# DressCode.net
KiCad netlist of a schematic drawn in EAGLE
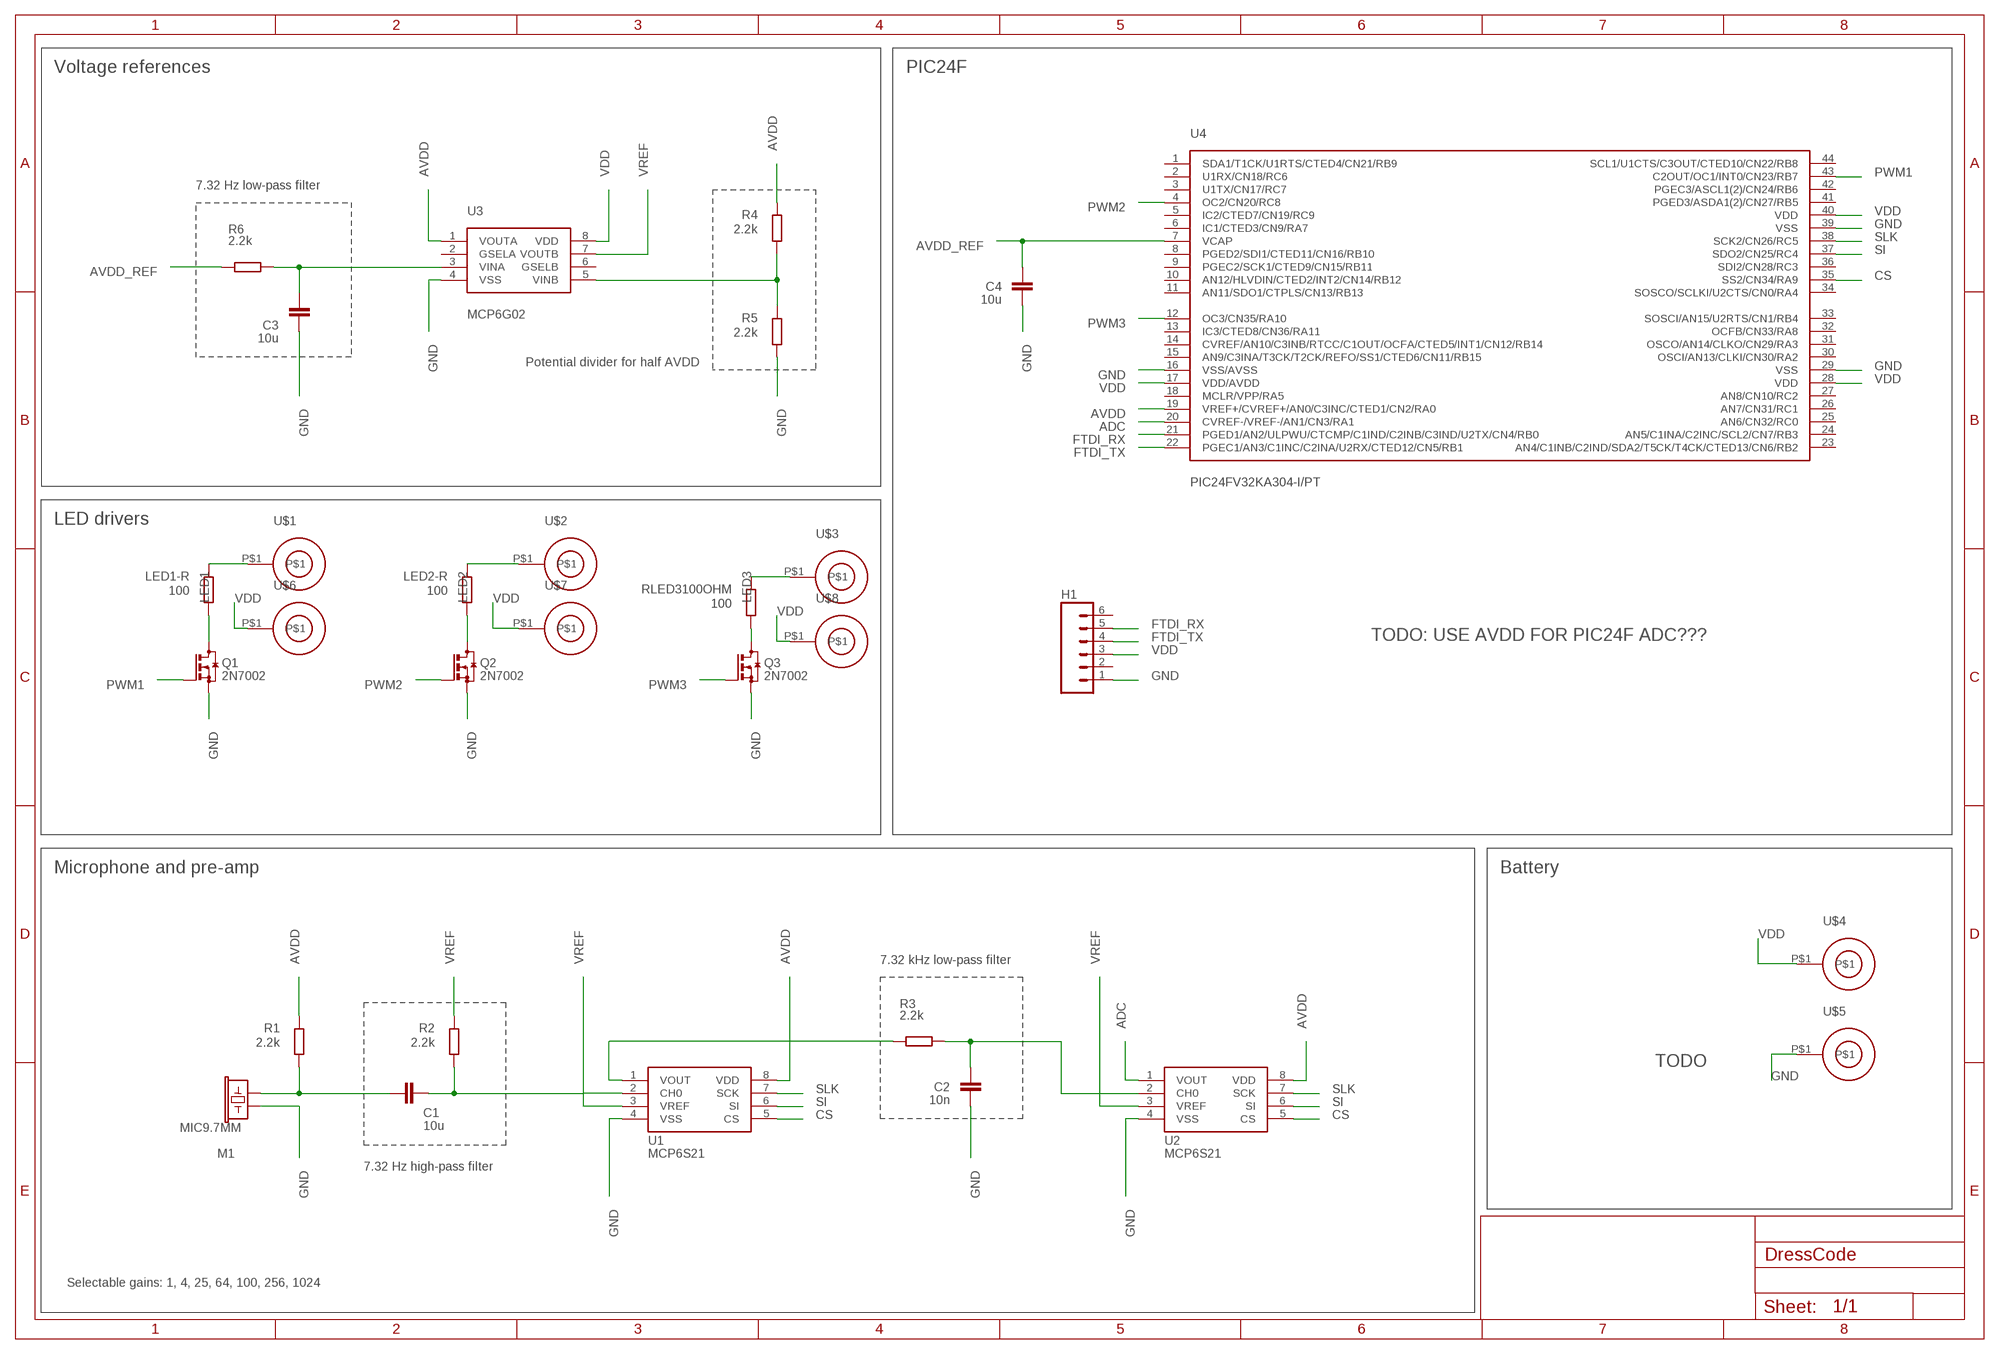
[diagram p0: schematic, sheet 1]

(export (version "E")
  (design (tool "Eeschema 10.0.6"))
  (components
    (comp (ref "C1")
      (value "10u")
      (footprint "eagle-import:C0805")
      (libsource (lib "eagle-import") (part "C-EUC0805"))
    )
    (comp (ref "C2")
      (value "10n")
      (footprint "eagle-import:C0805")
      (libsource (lib "eagle-import") (part "C-EUC0805"))
    )
    (comp (ref "C3")
      (value "10u")
      (footprint "eagle-import:C0805")
      (libsource (lib "eagle-import") (part "C-EUC0805"))
    )
    (comp (ref "C4")
      (value "10u")
      (footprint "eagle-import:C0805")
      (libsource (lib "eagle-import") (part "C-EUC0805"))
    )
    (comp (ref "H1")
      (value "M06LOCK")
      (footprint "eagle-import:1X06_LOCK")
      (libsource (lib "eagle-import") (part "M06LOCK"))
    )
    (comp (ref "LED1-R")
      (value "100")
      (footprint "eagle-import:R0805")
      (libsource (lib "eagle-import") (part "R-EU_R0805"))
    )
    (comp (ref "LED2-R")
      (value "100")
      (footprint "eagle-import:R0805")
      (libsource (lib "eagle-import") (part "R-EU_R0805"))
    )
    (comp (ref "M1")
      (value "MIC9.7MM")
      (footprint "eagle-import:MIC-9.7MM")
      (libsource (lib "eagle-import") (part "MIC9.7MM"))
    )
    (comp (ref "Q1")
      (value "2N7002")
      (footprint "eagle-import:SOT23")
      (libsource (lib "eagle-import") (part "BSS123"))
    )
    (comp (ref "Q2")
      (value "2N7002")
      (footprint "eagle-import:SOT23")
      (libsource (lib "eagle-import") (part "BSS123"))
    )
    (comp (ref "Q3")
      (value "2N7002")
      (footprint "eagle-import:SOT23")
      (libsource (lib "eagle-import") (part "BSS123"))
    )
    (comp (ref "R1")
      (value "2.2k")
      (footprint "eagle-import:R0805")
      (libsource (lib "eagle-import") (part "R-EU_R0805"))
    )
    (comp (ref "R2")
      (value "2.2k")
      (footprint "eagle-import:R0805")
      (libsource (lib "eagle-import") (part "R-EU_R0805"))
    )
    (comp (ref "R3")
      (value "2.2k")
      (footprint "eagle-import:R0805")
      (libsource (lib "eagle-import") (part "R-EU_R0805"))
    )
    (comp (ref "R4")
      (value "2.2k")
      (footprint "eagle-import:R0805")
      (libsource (lib "eagle-import") (part "R-EU_R0805"))
    )
    (comp (ref "R5")
      (value "2.2k")
      (footprint "eagle-import:R0805")
      (libsource (lib "eagle-import") (part "R-EU_R0805"))
    )
    (comp (ref "R6")
      (value "2.2k")
      (footprint "eagle-import:R0805")
      (libsource (lib "eagle-import") (part "R-EU_R0805"))
    )
    (comp (ref "RLED3100OHM")
      (value "100")
      (footprint "eagle-import:R0805")
      (libsource (lib "eagle-import") (part "R-EU_R0805"))
    )
    (comp (ref "U$1")
      (value "SEWING-VIA")
      (footprint "eagle-import:SEWING-VIA2MM")
      (libsource (lib "eagle-import") (part "SEWING-VIA"))
    )
    (comp (ref "U$2")
      (value "SEWING-VIA")
      (footprint "eagle-import:SEWING-VIA2MM")
      (libsource (lib "eagle-import") (part "SEWING-VIA"))
    )
    (comp (ref "U$3")
      (value "SEWING-VIA")
      (footprint "eagle-import:SEWING-VIA2MM")
      (libsource (lib "eagle-import") (part "SEWING-VIA"))
    )
    (comp (ref "U$4")
      (value "SEWING-VIA")
      (footprint "eagle-import:SEWING-VIA2MM")
      (libsource (lib "eagle-import") (part "SEWING-VIA"))
    )
    (comp (ref "U$5")
      (value "SEWING-VIA")
      (footprint "eagle-import:SEWING-VIA2MM")
      (libsource (lib "eagle-import") (part "SEWING-VIA"))
    )
    (comp (ref "U$6")
      (value "SEWING-VIA")
      (footprint "eagle-import:SEWING-VIA2MM")
      (libsource (lib "eagle-import") (part "SEWING-VIA"))
    )
    (comp (ref "U$7")
      (value "SEWING-VIA")
      (footprint "eagle-import:SEWING-VIA2MM")
      (libsource (lib "eagle-import") (part "SEWING-VIA"))
    )
    (comp (ref "U$8")
      (value "SEWING-VIA")
      (footprint "eagle-import:SEWING-VIA2MM")
      (libsource (lib "eagle-import") (part "SEWING-VIA"))
    )
    (comp (ref "U1")
      (value "MCP6S21")
      (footprint "eagle-import:SOIC-8")
      (libsource (lib "eagle-import") (part "MCP6S21"))
    )
    (comp (ref "U2")
      (value "MCP6S21")
      (footprint "eagle-import:SOIC-8")
      (libsource (lib "eagle-import") (part "MCP6S21"))
    )
    (comp (ref "U3")
      (value "MCP6G02")
      (footprint "eagle-import:SOIC-8")
      (libsource (lib "eagle-import") (part "MCP6G02"))
    )
    (comp (ref "U4")
      (value "PIC24FV32KA304-I/PT")
      (footprint "eagle-import:TQFP44")
      (libsource (lib "eagle-import") (part "PIC24FV32KA304-I/PT"))
    )
  )
  (nets
    (net (code "1") (name "/ADC") (class "Default")
      (node (ref "U2") (pin "1") (pinfunction "VOUT_1") (pintype "bidirectional"))
      (node (ref "U4") (pin "20") (pinfunction "CVREF-/VREF-/AN1/CN3/RA1_20") (pintype "bidirectional"))
    )
    (net (code "2") (name "/AVDD") (class "Default")
      (node (ref "R1") (pin "2") (pinfunction "2_2") (pintype "passive"))
      (node (ref "R4") (pin "2") (pinfunction "2_2") (pintype "passive"))
      (node (ref "U1") (pin "8") (pinfunction "VDD_8") (pintype "bidirectional"))
      (node (ref "U2") (pin "8") (pinfunction "VDD_8") (pintype "bidirectional"))
      (node (ref "U3") (pin "1") (pinfunction "VOUTA_1") (pintype "bidirectional"))
      (node (ref "U4") (pin "19") (pinfunction "VREF+/CVREF+/AN0/C3INC/CTED1/CN2/RA0_19") (pintype "bidirectional"))
    )
    (net (code "3") (name "/AVDD_REF") (class "Default")
      (node (ref "C4") (pin "2") (pinfunction "2_2") (pintype "passive"))
      (node (ref "R6") (pin "1") (pinfunction "1_1") (pintype "passive"))
      (node (ref "U4") (pin "7") (pinfunction "VCAP_7") (pintype "bidirectional"))
    )
    (net (code "4") (name "/CS") (class "Default")
      (node (ref "U1") (pin "5") (pinfunction "CS_5") (pintype "bidirectional"))
      (node (ref "U2") (pin "5") (pinfunction "CS_5") (pintype "bidirectional"))
      (node (ref "U4") (pin "35") (pinfunction "SS2/CN34/RA9_35") (pintype "bidirectional"))
    )
    (net (code "5") (name "/FTDI_RX") (class "Default")
      (node (ref "H1") (pin "5") (pinfunction "5_5") (pintype "passive"))
      (node (ref "U4") (pin "21") (pinfunction "PGED1/AN2/ULPWU/CTCMP/C1IND/C2INB/C3IND/U2TX/CN4/RB0_21") (pintype "bidirectional"))
    )
    (net (code "6") (name "/FTDI_TX") (class "Default")
      (node (ref "H1") (pin "4") (pinfunction "4_4") (pintype "passive"))
      (node (ref "U4") (pin "22") (pinfunction "PGEC1/AN3/C1INC/C2INA/U2RX/CTED12/CN5/RB1_22") (pintype "bidirectional"))
    )
    (net (code "7") (name "/GND") (class "Default")
      (node (ref "C2") (pin "2") (pinfunction "2_2") (pintype "passive"))
      (node (ref "C3") (pin "1") (pinfunction "1_1") (pintype "passive"))
      (node (ref "C4") (pin "1") (pinfunction "1_1") (pintype "passive"))
      (node (ref "H1") (pin "1") (pinfunction "1_1") (pintype "passive"))
      (node (ref "M1") (pin "2") (pinfunction "2_2") (pintype "passive"))
      (node (ref "Q1") (pin "2") (pinfunction "S_2") (pintype "passive"))
      (node (ref "Q2") (pin "2") (pinfunction "S_2") (pintype "passive"))
      (node (ref "Q3") (pin "2") (pinfunction "S_2") (pintype "passive"))
      (node (ref "R5") (pin "1") (pinfunction "1_1") (pintype "passive"))
      (node (ref "U$5") (pin "P$1") (pinfunction "P$1_P$1") (pintype "bidirectional"))
      (node (ref "U1") (pin "4") (pinfunction "VSS_4") (pintype "bidirectional"))
      (node (ref "U2") (pin "4") (pinfunction "VSS_4") (pintype "bidirectional"))
      (node (ref "U3") (pin "4") (pinfunction "VSS_4") (pintype "bidirectional"))
      (node (ref "U4") (pin "16") (pinfunction "VSS/AVSS_16") (pintype "bidirectional"))
      (node (ref "U4") (pin "29") (pinfunction "VSS_29") (pintype "bidirectional"))
      (node (ref "U4") (pin "39") (pinfunction "VSS_39") (pintype "bidirectional"))
    )
    (net (code "8") (name "/LED1") (class "Default")
      (node (ref "LED1-R") (pin "2") (pinfunction "2_2") (pintype "passive"))
      (node (ref "U$1") (pin "P$1") (pinfunction "P$1_P$1") (pintype "bidirectional"))
    )
    (net (code "9") (name "/LED2") (class "Default")
      (node (ref "LED2-R") (pin "2") (pinfunction "2_2") (pintype "passive"))
      (node (ref "U$2") (pin "P$1") (pinfunction "P$1_P$1") (pintype "bidirectional"))
    )
    (net (code "10") (name "/LED3") (class "Default")
      (node (ref "RLED3100OHM") (pin "2") (pinfunction "2_2") (pintype "passive"))
      (node (ref "U$3") (pin "P$1") (pinfunction "P$1_P$1") (pintype "bidirectional"))
    )
    (net (code "11") (name "/PWM1") (class "Default")
      (node (ref "Q1") (pin "1") (pinfunction "G_1") (pintype "passive"))
      (node (ref "U4") (pin "43") (pinfunction "C2OUT/OC1/INT0/CN23/RB7_43") (pintype "bidirectional"))
    )
    (net (code "12") (name "/PWM2") (class "Default")
      (node (ref "Q2") (pin "1") (pinfunction "G_1") (pintype "passive"))
      (node (ref "U4") (pin "4") (pinfunction "OC2/CN20/RC8_4") (pintype "bidirectional"))
    )
    (net (code "13") (name "/PWM3") (class "Default")
      (node (ref "Q3") (pin "1") (pinfunction "G_1") (pintype "passive"))
      (node (ref "U4") (pin "12") (pinfunction "OC3/CN35/RA10_12") (pintype "bidirectional"))
    )
    (net (code "14") (name "/SI") (class "Default")
      (node (ref "U1") (pin "6") (pinfunction "SI_6") (pintype "bidirectional"))
      (node (ref "U2") (pin "6") (pinfunction "SI_6") (pintype "bidirectional"))
      (node (ref "U4") (pin "37") (pinfunction "SDO2/CN25/RC4_37") (pintype "bidirectional"))
    )
    (net (code "15") (name "/SLK") (class "Default")
      (node (ref "U1") (pin "7") (pinfunction "SCK_7") (pintype "bidirectional"))
      (node (ref "U2") (pin "7") (pinfunction "SCK_7") (pintype "bidirectional"))
      (node (ref "U4") (pin "38") (pinfunction "SCK2/CN26/RC5_38") (pintype "bidirectional"))
    )
    (net (code "16") (name "/VDD") (class "Default")
      (node (ref "H1") (pin "3") (pinfunction "3_3") (pintype "passive"))
      (node (ref "U$4") (pin "P$1") (pinfunction "P$1_P$1") (pintype "bidirectional"))
      (node (ref "U$6") (pin "P$1") (pinfunction "P$1_P$1") (pintype "bidirectional"))
      (node (ref "U$7") (pin "P$1") (pinfunction "P$1_P$1") (pintype "bidirectional"))
      (node (ref "U$8") (pin "P$1") (pinfunction "P$1_P$1") (pintype "bidirectional"))
      (node (ref "U3") (pin "8") (pinfunction "VDD_8") (pintype "bidirectional"))
      (node (ref "U4") (pin "17") (pinfunction "VDD/AVDD_17") (pintype "bidirectional"))
      (node (ref "U4") (pin "28") (pinfunction "VDD_28") (pintype "bidirectional"))
      (node (ref "U4") (pin "40") (pinfunction "VDD_40") (pintype "bidirectional"))
    )
    (net (code "17") (name "/VREF") (class "Default")
      (node (ref "R2") (pin "2") (pinfunction "2_2") (pintype "passive"))
      (node (ref "U1") (pin "3") (pinfunction "VREF_3") (pintype "bidirectional"))
      (node (ref "U2") (pin "3") (pinfunction "VREF_3") (pintype "bidirectional"))
      (node (ref "U3") (pin "7") (pinfunction "VOUTB_7") (pintype "bidirectional"))
    )
    (net (code "18") (name "Net-(C1-Pad1)") (class "Default")
      (node (ref "C1") (pin "1") (pinfunction "1_1") (pintype "passive"))
      (node (ref "M1") (pin "1") (pinfunction "1_1") (pintype "passive"))
      (node (ref "R1") (pin "1") (pinfunction "1_1") (pintype "passive"))
    )
    (net (code "19") (name "Net-(Q1-D)") (class "Default")
      (node (ref "LED1-R") (pin "1") (pinfunction "1_1") (pintype "passive"))
      (node (ref "Q1") (pin "3") (pinfunction "D_3") (pintype "passive"))
    )
    (net (code "20") (name "Net-(Q2-D)") (class "Default")
      (node (ref "LED2-R") (pin "1") (pinfunction "1_1") (pintype "passive"))
      (node (ref "Q2") (pin "3") (pinfunction "D_3") (pintype "passive"))
    )
    (net (code "21") (name "Net-(Q3-D)") (class "Default")
      (node (ref "Q3") (pin "3") (pinfunction "D_3") (pintype "passive"))
      (node (ref "RLED3100OHM") (pin "1") (pinfunction "1_1") (pintype "passive"))
    )
    (net (code "22") (name "Net-(U1-CH0)") (class "Default")
      (node (ref "C1") (pin "2") (pinfunction "2_2") (pintype "passive"))
      (node (ref "R2") (pin "1") (pinfunction "1_1") (pintype "passive"))
      (node (ref "U1") (pin "2") (pinfunction "CH0_2") (pintype "bidirectional"))
    )
    (net (code "23") (name "Net-(U1-VOUT)") (class "Default")
      (node (ref "R3") (pin "1") (pinfunction "1_1") (pintype "passive"))
      (node (ref "U1") (pin "1") (pinfunction "VOUT_1") (pintype "bidirectional"))
    )
    (net (code "24") (name "Net-(U2-CH0)") (class "Default")
      (node (ref "C2") (pin "1") (pinfunction "1_1") (pintype "passive"))
      (node (ref "R3") (pin "2") (pinfunction "2_2") (pintype "passive"))
      (node (ref "U2") (pin "2") (pinfunction "CH0_2") (pintype "bidirectional"))
    )
    (net (code "25") (name "Net-(U3-VINA)") (class "Default")
      (node (ref "C3") (pin "2") (pinfunction "2_2") (pintype "passive"))
      (node (ref "R6") (pin "2") (pinfunction "2_2") (pintype "passive"))
      (node (ref "U3") (pin "3") (pinfunction "VINA_3") (pintype "bidirectional"))
    )
    (net (code "26") (name "Net-(U3-VINB)") (class "Default")
      (node (ref "R4") (pin "1") (pinfunction "1_1") (pintype "passive"))
      (node (ref "R5") (pin "2") (pinfunction "2_2") (pintype "passive"))
      (node (ref "U3") (pin "5") (pinfunction "VINB_5") (pintype "bidirectional"))
    )
    (net (code "27") (name "unconnected-(H1-Pad2)") (class "Default")
      (node (ref "H1") (pin "2") (pinfunction "2_2") (pintype "passive"))
    )
    (net (code "28") (name "unconnected-(H1-Pad6)") (class "Default")
      (node (ref "H1") (pin "6") (pinfunction "6_6") (pintype "passive"))
    )
    (net (code "29") (name "unconnected-(U3-GSELA-Pad2)") (class "Default")
      (node (ref "U3") (pin "2") (pinfunction "GSELA_2") (pintype "bidirectional"))
    )
    (net (code "30") (name "unconnected-(U3-GSELB-Pad6)") (class "Default")
      (node (ref "U3") (pin "6") (pinfunction "GSELB_6") (pintype "bidirectional"))
    )
    (net (code "31") (name "unconnected-(U4-AN4{slash}C1INB{slash}C2IND{slash}SDA2{slash}T5CK{slash}T4CK{slash}CTED13{slash}CN6{slash}RB2-Pad23)") (class "Default")
      (node (ref "U4") (pin "23") (pinfunction "AN4/C1INB/C2IND/SDA2/T5CK/T4CK/CTED13/CN6/RB2_23") (pintype "bidirectional"))
    )
    (net (code "32") (name "unconnected-(U4-AN5{slash}C1INA{slash}C2INC{slash}SCL2{slash}CN7{slash}RB3-Pad24)") (class "Default")
      (node (ref "U4") (pin "24") (pinfunction "AN5/C1INA/C2INC/SCL2/CN7/RB3_24") (pintype "bidirectional"))
    )
    (net (code "33") (name "unconnected-(U4-AN6{slash}CN32{slash}RC0-Pad25)") (class "Default")
      (node (ref "U4") (pin "25") (pinfunction "AN6/CN32/RC0_25") (pintype "bidirectional"))
    )
    (net (code "34") (name "unconnected-(U4-AN7{slash}CN31{slash}RC1-Pad26)") (class "Default")
      (node (ref "U4") (pin "26") (pinfunction "AN7/CN31/RC1_26") (pintype "bidirectional"))
    )
    (net (code "35") (name "unconnected-(U4-AN8{slash}CN10{slash}RC2-Pad27)") (class "Default")
      (node (ref "U4") (pin "27") (pinfunction "AN8/CN10/RC2_27") (pintype "bidirectional"))
    )
    (net (code "36") (name "unconnected-(U4-AN9{slash}C3INA{slash}T3CK{slash}T2CK{slash}REFO{slash}SS1{slash}CTED6{slash}CN11{slash}RB15-Pad15)") (class "Default")
      (node (ref "U4") (pin "15") (pinfunction "AN9/C3INA/T3CK/T2CK/REFO/SS1/CTED6/CN11/RB15_15") (pintype "bidirectional"))
    )
    (net (code "37") (name "unconnected-(U4-AN11{slash}SDO1{slash}CTPLS{slash}CN13{slash}RB13-Pad11)") (class "Default")
      (node (ref "U4") (pin "11") (pinfunction "AN11/SDO1/CTPLS/CN13/RB13_11") (pintype "bidirectional"))
    )
    (net (code "38") (name "unconnected-(U4-AN12{slash}HLVDIN{slash}CTED2{slash}INT2{slash}CN14{slash}RB12-Pad10)") (class "Default")
      (node (ref "U4") (pin "10") (pinfunction "AN12/HLVDIN/CTED2/INT2/CN14/RB12_10") (pintype "bidirectional"))
    )
    (net (code "39") (name "unconnected-(U4-CVREF{slash}AN10{slash}C3INB{slash}RTCC{slash}C1OUT{slash}OCFA{slash}CTED5{slash}INT1{slash}CN12{slash}RB14-Pad14)") (class "Default")
      (node (ref "U4") (pin "14") (pinfunction "CVREF/AN10/C3INB/RTCC/C1OUT/OCFA/CTED5/INT1/CN12/RB14_14") (pintype "bidirectional"))
    )
    (net (code "40") (name "unconnected-(U4-IC1{slash}CTED3{slash}CN9{slash}RA7-Pad6)") (class "Default")
      (node (ref "U4") (pin "6") (pinfunction "IC1/CTED3/CN9/RA7_6") (pintype "bidirectional"))
    )
    (net (code "41") (name "unconnected-(U4-IC2{slash}CTED7{slash}CN19{slash}RC9-Pad5)") (class "Default")
      (node (ref "U4") (pin "5") (pinfunction "IC2/CTED7/CN19/RC9_5") (pintype "bidirectional"))
    )
    (net (code "42") (name "unconnected-(U4-IC3{slash}CTED8{slash}CN36{slash}RA11-Pad13)") (class "Default")
      (node (ref "U4") (pin "13") (pinfunction "IC3/CTED8/CN36/RA11_13") (pintype "bidirectional"))
    )
    (net (code "43") (name "unconnected-(U4-MCLR{slash}VPP{slash}RA5-Pad18)") (class "Default")
      (node (ref "U4") (pin "18") (pinfunction "MCLR/VPP/RA5_18") (pintype "bidirectional"))
    )
    (net (code "44") (name "unconnected-(U4-OCFB{slash}CN33{slash}RA8-Pad32)") (class "Default")
      (node (ref "U4") (pin "32") (pinfunction "OCFB/CN33/RA8_32") (pintype "bidirectional"))
    )
    (net (code "45") (name "unconnected-(U4-OSCI{slash}AN13{slash}CLKI{slash}CN30{slash}RA2-Pad30)") (class "Default")
      (node (ref "U4") (pin "30") (pinfunction "OSCI/AN13/CLKI/CN30/RA2_30") (pintype "bidirectional"))
    )
    (net (code "46") (name "unconnected-(U4-OSCO{slash}AN14{slash}CLKO{slash}CN29{slash}RA3-Pad31)") (class "Default")
      (node (ref "U4") (pin "31") (pinfunction "OSCO/AN14/CLKO/CN29/RA3_31") (pintype "bidirectional"))
    )
    (net (code "47") (name "unconnected-(U4-PGEC2{slash}SCK1{slash}CTED9{slash}CN15{slash}RB11-Pad9)") (class "Default")
      (node (ref "U4") (pin "9") (pinfunction "PGEC2/SCK1/CTED9/CN15/RB11_9") (pintype "bidirectional"))
    )
    (net (code "48") (name "unconnected-(U4-PGEC3{slash}ASCL1(2){slash}CN24{slash}RB6-Pad42)") (class "Default")
      (node (ref "U4") (pin "42") (pinfunction "PGEC3/ASCL1(2)/CN24/RB6_42") (pintype "bidirectional"))
    )
    (net (code "49") (name "unconnected-(U4-PGED2{slash}SDI1{slash}CTED11{slash}CN16{slash}RB10-Pad8)") (class "Default")
      (node (ref "U4") (pin "8") (pinfunction "PGED2/SDI1/CTED11/CN16/RB10_8") (pintype "bidirectional"))
    )
    (net (code "50") (name "unconnected-(U4-PGED3{slash}ASDA1(2){slash}CN27{slash}RB5-Pad41)") (class "Default")
      (node (ref "U4") (pin "41") (pinfunction "PGED3/ASDA1(2)/CN27/RB5_41") (pintype "bidirectional"))
    )
    (net (code "51") (name "unconnected-(U4-SCL1{slash}U1CTS{slash}C3OUT{slash}CTED10{slash}CN22{slash}RB8-Pad44)") (class "Default")
      (node (ref "U4") (pin "44") (pinfunction "SCL1/U1CTS/C3OUT/CTED10/CN22/RB8_44") (pintype "bidirectional"))
    )
    (net (code "52") (name "unconnected-(U4-SDA1{slash}T1CK{slash}U1RTS{slash}CTED4{slash}CN21{slash}RB9-Pad1)") (class "Default")
      (node (ref "U4") (pin "1") (pinfunction "SDA1/T1CK/U1RTS/CTED4/CN21/RB9_1") (pintype "bidirectional"))
    )
    (net (code "53") (name "unconnected-(U4-SDI2{slash}CN28{slash}RC3-Pad36)") (class "Default")
      (node (ref "U4") (pin "36") (pinfunction "SDI2/CN28/RC3_36") (pintype "bidirectional"))
    )
    (net (code "54") (name "unconnected-(U4-SOSCI{slash}AN15{slash}U2RTS{slash}CN1{slash}RB4-Pad33)") (class "Default")
      (node (ref "U4") (pin "33") (pinfunction "SOSCI/AN15/U2RTS/CN1/RB4_33") (pintype "bidirectional"))
    )
    (net (code "55") (name "unconnected-(U4-SOSCO{slash}SCLKI{slash}U2CTS{slash}CN0{slash}RA4-Pad34)") (class "Default")
      (node (ref "U4") (pin "34") (pinfunction "SOSCO/SCLKI/U2CTS/CN0/RA4_34") (pintype "bidirectional"))
    )
    (net (code "56") (name "unconnected-(U4-U1RX{slash}CN18{slash}RC6-Pad2)") (class "Default")
      (node (ref "U4") (pin "2") (pinfunction "U1RX/CN18/RC6_2") (pintype "bidirectional"))
    )
    (net (code "57") (name "unconnected-(U4-U1TX{slash}CN17{slash}RC7-Pad3)") (class "Default")
      (node (ref "U4") (pin "3") (pinfunction "U1TX/CN17/RC7_3") (pintype "bidirectional"))
    )
  )
)
